# switch-fuses.net
KiCad netlist of a schematic drawn in EAGLE
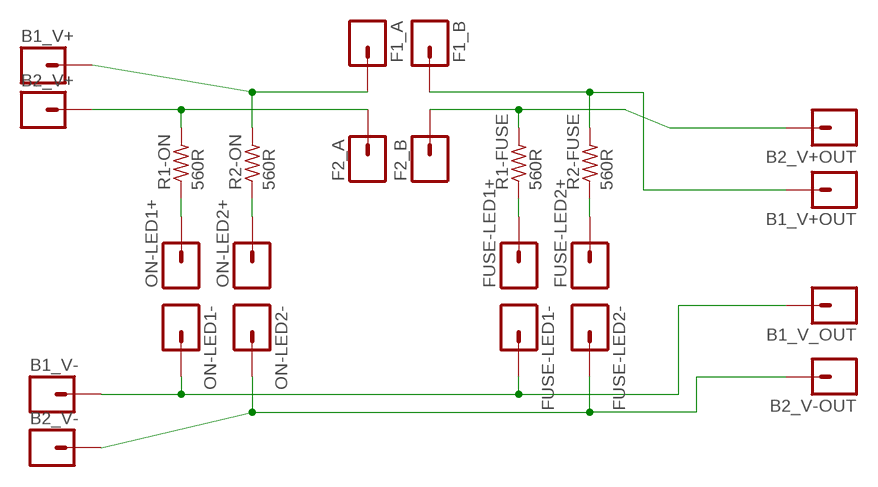
[diagram p0: schematic, sheet 1]

(export (version "E")
  (design (tool "Eeschema 10.0.6"))
  (components
    (comp (ref "B1_V+")
      (value "1-HOLE2.5MM")
      (footprint "eagle-import:1-HOLE-2.5MM")
      (libsource (lib "eagle-import") (part "1-HOLE2.5MM"))
    )
    (comp (ref "B1_V+OUT")
      (value "1-HOLE2.5MM")
      (footprint "eagle-import:1-HOLE-2.5MM")
      (libsource (lib "eagle-import") (part "1-HOLE2.5MM"))
    )
    (comp (ref "B1_V-")
      (value "1-HOLE2.5MM")
      (footprint "eagle-import:1-HOLE-2.5MM")
      (libsource (lib "eagle-import") (part "1-HOLE2.5MM"))
    )
    (comp (ref "B1_V_OUT")
      (value "1-HOLE2.5MM")
      (footprint "eagle-import:1-HOLE-2.5MM")
      (libsource (lib "eagle-import") (part "1-HOLE2.5MM"))
    )
    (comp (ref "B2_V+")
      (value "1-HOLE2.5MM")
      (footprint "eagle-import:1-HOLE-2.5MM")
      (libsource (lib "eagle-import") (part "1-HOLE2.5MM"))
    )
    (comp (ref "B2_V+OUT")
      (value "1-HOLE2.5MM")
      (footprint "eagle-import:1-HOLE-2.5MM")
      (libsource (lib "eagle-import") (part "1-HOLE2.5MM"))
    )
    (comp (ref "B2_V-")
      (value "1-HOLE2.5MM")
      (footprint "eagle-import:1-HOLE-2.5MM")
      (libsource (lib "eagle-import") (part "1-HOLE2.5MM"))
    )
    (comp (ref "B2_V-OUT")
      (value "1-HOLE2.5MM")
      (footprint "eagle-import:1-HOLE-2.5MM")
      (libsource (lib "eagle-import") (part "1-HOLE2.5MM"))
    )
    (comp (ref "F1_A")
      (value "1-HOLE2.5MM")
      (footprint "eagle-import:1-HOLE-2.5MM")
      (libsource (lib "eagle-import") (part "1-HOLE2.5MM"))
    )
    (comp (ref "F1_B")
      (value "1-HOLE2.5MM")
      (footprint "eagle-import:1-HOLE-2.5MM")
      (libsource (lib "eagle-import") (part "1-HOLE2.5MM"))
    )
    (comp (ref "F2_A")
      (value "1-HOLE2.5MM")
      (footprint "eagle-import:1-HOLE-2.5MM")
      (libsource (lib "eagle-import") (part "1-HOLE2.5MM"))
    )
    (comp (ref "F2_B")
      (value "1-HOLE2.5MM")
      (footprint "eagle-import:1-HOLE-2.5MM")
      (libsource (lib "eagle-import") (part "1-HOLE2.5MM"))
    )
    (comp (ref "FUSE-LED1+")
      (value "1-HOLE0.8MM")
      (footprint "eagle-import:1-HOLE")
      (libsource (lib "eagle-import") (part "1-HOLE0.8MM"))
    )
    (comp (ref "FUSE-LED1-")
      (value "1-HOLE0.8MM")
      (footprint "eagle-import:1-HOLE")
      (libsource (lib "eagle-import") (part "1-HOLE0.8MM"))
    )
    (comp (ref "FUSE-LED2+")
      (value "1-HOLE0.8MM")
      (footprint "eagle-import:1-HOLE")
      (libsource (lib "eagle-import") (part "1-HOLE0.8MM"))
    )
    (comp (ref "FUSE-LED2-")
      (value "1-HOLE0.8MM")
      (footprint "eagle-import:1-HOLE")
      (libsource (lib "eagle-import") (part "1-HOLE0.8MM"))
    )
    (comp (ref "ON-LED1+")
      (value "1-HOLE0.8MM")
      (footprint "eagle-import:1-HOLE")
      (libsource (lib "eagle-import") (part "1-HOLE0.8MM"))
    )
    (comp (ref "ON-LED1-")
      (value "1-HOLE0.8MM")
      (footprint "eagle-import:1-HOLE")
      (libsource (lib "eagle-import") (part "1-HOLE0.8MM"))
    )
    (comp (ref "ON-LED2+")
      (value "1-HOLE0.8MM")
      (footprint "eagle-import:1-HOLE")
      (libsource (lib "eagle-import") (part "1-HOLE0.8MM"))
    )
    (comp (ref "ON-LED2-")
      (value "1-HOLE0.8MM")
      (footprint "eagle-import:1-HOLE")
      (libsource (lib "eagle-import") (part "1-HOLE0.8MM"))
    )
    (comp (ref "R1-FUSE")
      (value "560R")
      (footprint "eagle-import:0309_15")
      (libsource (lib "eagle-import") (part "RESISTOR0309/15"))
    )
    (comp (ref "R1-ON")
      (value "560R")
      (footprint "eagle-import:0309_15")
      (libsource (lib "eagle-import") (part "RESISTOR0309/15"))
    )
    (comp (ref "R2-FUSE")
      (value "560R")
      (footprint "eagle-import:0309_15")
      (libsource (lib "eagle-import") (part "RESISTOR0309/15"))
    )
    (comp (ref "R2-ON")
      (value "560R")
      (footprint "eagle-import:0309_15")
      (libsource (lib "eagle-import") (part "RESISTOR0309/15"))
    )
  )
  (nets
    (net (code "1") (name "Net-(B1_V+-1)") (class "Default")
      (node (ref "B1_V+") (pin "P$1") (pinfunction "1_P$1") (pintype "passive"))
      (node (ref "F1_A") (pin "P$1") (pinfunction "1_P$1") (pintype "passive"))
      (node (ref "R2-ON") (pin "2") (pinfunction "2_2") (pintype "passive"))
    )
    (net (code "2") (name "Net-(B1_V+OUT-1)") (class "Default")
      (node (ref "B1_V+OUT") (pin "P$1") (pinfunction "1_P$1") (pintype "passive"))
      (node (ref "F1_B") (pin "P$1") (pinfunction "1_P$1") (pintype "passive"))
      (node (ref "R2-FUSE") (pin "2") (pinfunction "2_2") (pintype "passive"))
    )
    (net (code "3") (name "Net-(B1_V--1)") (class "Default")
      (node (ref "B1_V-") (pin "P$1") (pinfunction "1_P$1") (pintype "passive"))
      (node (ref "B1_V_OUT") (pin "P$1") (pinfunction "1_P$1") (pintype "passive"))
      (node (ref "FUSE-LED1-") (pin "1") (pinfunction "1_1") (pintype "passive"))
      (node (ref "ON-LED1-") (pin "1") (pinfunction "1_1") (pintype "passive"))
    )
    (net (code "4") (name "Net-(B2_V+-1)") (class "Default")
      (node (ref "B2_V+") (pin "P$1") (pinfunction "1_P$1") (pintype "passive"))
      (node (ref "F2_A") (pin "P$1") (pinfunction "1_P$1") (pintype "passive"))
      (node (ref "R1-ON") (pin "2") (pinfunction "2_2") (pintype "passive"))
    )
    (net (code "5") (name "Net-(B2_V+OUT-1)") (class "Default")
      (node (ref "B2_V+OUT") (pin "P$1") (pinfunction "1_P$1") (pintype "passive"))
      (node (ref "F2_B") (pin "P$1") (pinfunction "1_P$1") (pintype "passive"))
      (node (ref "R1-FUSE") (pin "2") (pinfunction "2_2") (pintype "passive"))
    )
    (net (code "6") (name "Net-(B2_V--1)") (class "Default")
      (node (ref "B2_V-") (pin "P$1") (pinfunction "1_P$1") (pintype "passive"))
      (node (ref "B2_V-OUT") (pin "P$1") (pinfunction "1_P$1") (pintype "passive"))
      (node (ref "FUSE-LED2-") (pin "1") (pinfunction "1_1") (pintype "passive"))
      (node (ref "ON-LED2-") (pin "1") (pinfunction "1_1") (pintype "passive"))
    )
    (net (code "7") (name "Net-(FUSE-LED1+-Pad1)") (class "Default")
      (node (ref "FUSE-LED1+") (pin "1") (pinfunction "1_1") (pintype "passive"))
      (node (ref "R1-FUSE") (pin "1") (pinfunction "1_1") (pintype "passive"))
    )
    (net (code "8") (name "Net-(FUSE-LED2+-Pad1)") (class "Default")
      (node (ref "FUSE-LED2+") (pin "1") (pinfunction "1_1") (pintype "passive"))
      (node (ref "R2-FUSE") (pin "1") (pinfunction "1_1") (pintype "passive"))
    )
    (net (code "9") (name "Net-(ON-LED1+-Pad1)") (class "Default")
      (node (ref "ON-LED1+") (pin "1") (pinfunction "1_1") (pintype "passive"))
      (node (ref "R1-ON") (pin "1") (pinfunction "1_1") (pintype "passive"))
    )
    (net (code "10") (name "Net-(ON-LED2+-Pad1)") (class "Default")
      (node (ref "ON-LED2+") (pin "1") (pinfunction "1_1") (pintype "passive"))
      (node (ref "R2-ON") (pin "1") (pinfunction "1_1") (pintype "passive"))
    )
  )
)
